# cpu.net
KiCad netlist of a schematic drawn in Altium Designer
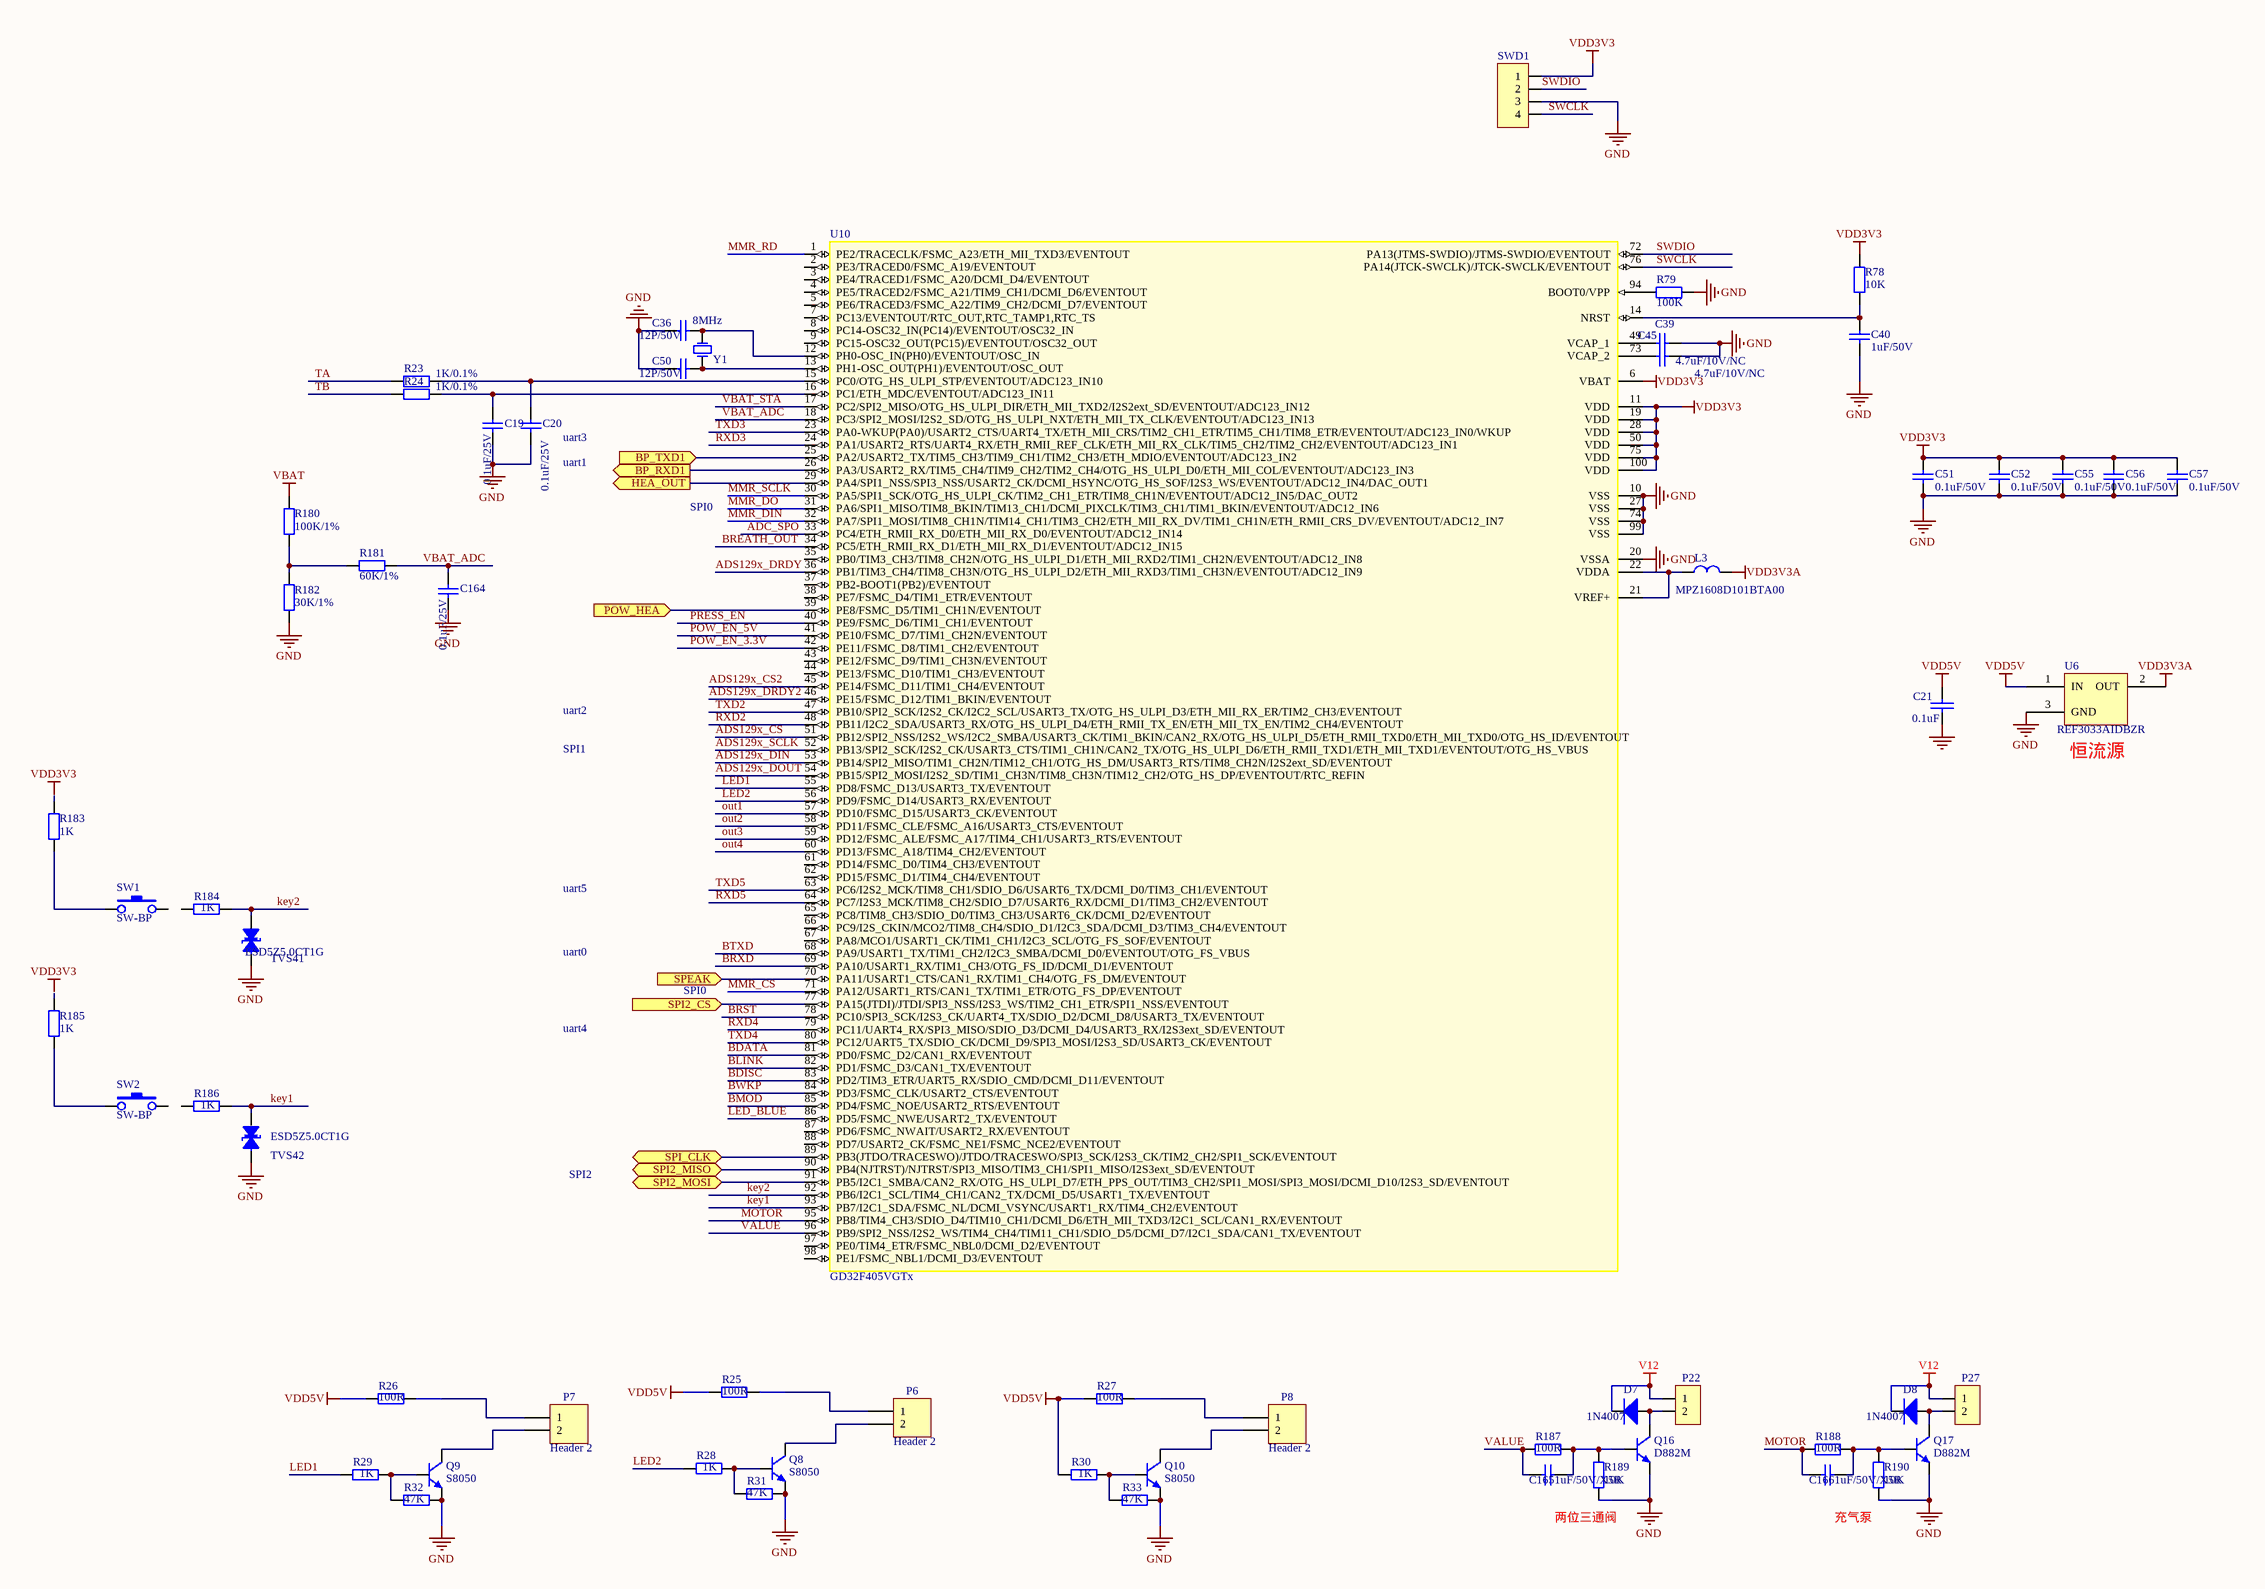
[diagram p0: cpu.SchDoc]

(export (version "E")
  (design (tool "Eeschema 10.0.6"))
  (components
    (comp (ref "C19")
      (value "0.1uF/25V")
      (footprint "SMD-0603C")
      (description "贴片电容 5%")
      (libsource (lib "XiaoyI") (part "CAP4"))
    )
    (comp (ref "C20")
      (value "0.1uF/25V")
      (footprint "SMD-0603C")
      (description "贴片电容 5%")
      (libsource (lib "XiaoyI") (part "CAP4"))
    )
    (comp (ref "C21")
      (value "0.1uF")
      (footprint "0603C")
      (description "Capacitor")
      (libsource (lib "*") (part "CAP"))
    )
    (comp (ref "C36")
      (value "12P/50V")
      (footprint "SMD-0603C")
      (description "贴片电容 5%")
      (libsource (lib "XiaoyI") (part "CAP4"))
    )
    (comp (ref "C39")
      (value "4.7uF/10V/NC")
      (footprint "SMD-0603C")
      (description "贴片电容 20%")
      (libsource (lib "XiaoyI") (part "CAP4"))
    )
    (comp (ref "C40")
      (value "1uF/50V")
      (footprint "SMD-0603C")
      (description "贴片电容 20%")
      (libsource (lib "XiaoyI") (part "CAP4"))
    )
    (comp (ref "C45")
      (value "4.7uF/10V/NC")
      (footprint "SMD-0603C")
      (description "贴片电容 20%")
      (libsource (lib "XiaoyI") (part "CAP4"))
    )
    (comp (ref "C50")
      (value "12P/50V")
      (footprint "SMD-0603C")
      (description "贴片电容 5%")
      (libsource (lib "XiaoyI") (part "CAP4"))
    )
    (comp (ref "C51")
      (value "0.1uF/50V")
      (footprint "SMD-0603C")
      (description "贴片电容 20%")
      (libsource (lib "XiaoyI") (part "CAP4"))
    )
    (comp (ref "C52")
      (value "0.1uF/50V")
      (footprint "SMD-0603C")
      (description "贴片电容 20%")
      (libsource (lib "XiaoyI") (part "CAP4"))
    )
    (comp (ref "C55")
      (value "0.1uF/50V")
      (footprint "SMD-0603C")
      (description "贴片电容 20%")
      (libsource (lib "XiaoyI") (part "CAP4"))
    )
    (comp (ref "C56")
      (value "0.1uF/50V")
      (footprint "SMD-0603C")
      (description "贴片电容 20%")
      (libsource (lib "XiaoyI") (part "CAP4"))
    )
    (comp (ref "C57")
      (value "0.1uF/50V")
      (footprint "SMD-0603C")
      (description "贴片电容 20%")
      (libsource (lib "XiaoyI") (part "CAP4"))
    )
    (comp (ref "C164")
      (value "0.1uF/25V")
      (footprint "SMD-0603C")
      (description "贴片电容 5%")
      (libsource (lib "XiaoyI") (part "CAP4"))
    )
    (comp (ref "C165")
      (value "1uF/50V/X5R")
      (footprint "SMD-0603C")
      (description "贴片电容 20%")
      (libsource (lib "XiaoyI") (part "CAP4"))
    )
    (comp (ref "C166")
      (value "1uF/50V/X5R")
      (footprint "SMD-0603C")
      (description "贴片电容 20%")
      (libsource (lib "XiaoyI") (part "CAP4"))
    )
    (comp (ref "D7")
      (value "1N4007")
      (footprint "DO-214-AC")
      (description "二极管 M7")
      (libsource (lib "XiaoyI") (part "DIODE2"))
    )
    (comp (ref "D8")
      (value "1N4007")
      (footprint "DO-214-AC")
      (description "二极管 M7")
      (libsource (lib "XiaoyI") (part "DIODE2"))
    )
    (comp (ref "L3")
      (value "MPZ1608D101BTA00")
      (footprint "SMD-0603")
      (description "磁珠电感 100R 100MHz")
      (libsource (lib "XiaoyI") (part "CIZHU1"))
    )
    (comp (ref "P6")
      (value "Header 2")
      (footprint "2X2.54MMZ")
      (description "Header, 2-Pin")
      (fields (field (name "PUBLISHER") "Altium Limited"))
      (libsource (lib "Miscellaneous Connectors") (part "Header 2"))
    )
    (comp (ref "P7")
      (value "Header 2")
      (footprint "2X2.54MMZ")
      (description "Header, 2-Pin")
      (fields (field (name "PUBLISHER") "Altium Limited"))
      (libsource (lib "Miscellaneous Connectors") (part "Header 2"))
    )
    (comp (ref "P8")
      (value "Header 2")
      (footprint "2X2.54MMZ")
      (description "Header, 2-Pin")
      (fields (field (name "PUBLISHER") "Altium Limited"))
      (libsource (lib "Miscellaneous Connectors") (part "Header 2"))
    )
    (comp (ref "P22")
      (value "VH2.54-2P")
      (footprint "2X2.54MMZ")
      (description "2.54mm- 2P立贴")
      (libsource (lib "XiaoyI") (part "SIP-2"))
    )
    (comp (ref "P27")
      (value "VH2.54-2P")
      (footprint "2X2.54MMZ")
      (description "2.54mm- 2P立贴")
      (libsource (lib "XiaoyI") (part "SIP-2"))
    )
    (comp (ref "Q8")
      (value "S8050")
      (footprint "SOT-23")
      (description "NPN")
      (libsource (lib "XiaoyI") (part "NPN-1"))
    )
    (comp (ref "Q9")
      (value "S8050")
      (footprint "SOT-23")
      (description "NPN")
      (libsource (lib "XiaoyI") (part "NPN-1"))
    )
    (comp (ref "Q10")
      (value "S8050")
      (footprint "SOT-23")
      (description "NPN")
      (libsource (lib "XiaoyI") (part "NPN-1"))
    )
    (comp (ref "Q16")
      (value "D882M")
      (footprint "SOT-89-3")
      (description "NPN TO252")
      (libsource (lib "XiaoyI") (part "NPN-TO252"))
    )
    (comp (ref "Q17")
      (value "D882M")
      (footprint "SOT-89-3")
      (description "NPN TO252")
      (libsource (lib "XiaoyI") (part "NPN-TO252"))
    )
    (comp (ref "R23")
      (value "1K/0.1%")
      (footprint "SMD-0603")
      (description "贴片电阻 1%")
      (libsource (lib "") (part "RES2_2"))
    )
    (comp (ref "R24")
      (value "1K/0.1%")
      (footprint "SMD-0603")
      (description "贴片电阻 1%")
      (libsource (lib "") (part "RES2_2"))
    )
    (comp (ref "R25")
      (value "100R")
      (footprint "SMD-0805")
      (description "贴片电阻 5%")
      (libsource (lib "") (part "RES0_1"))
    )
    (comp (ref "R26")
      (value "100R")
      (footprint "SMD-0805")
      (description "贴片电阻 5%")
      (libsource (lib "") (part "RES0_1"))
    )
    (comp (ref "R27")
      (value "100R")
      (footprint "SMD-0805")
      (description "贴片电阻 5%")
      (libsource (lib "") (part "RES0_1"))
    )
    (comp (ref "R28")
      (value "1K")
      (footprint "SMD-0603")
      (description "贴片电阻 5%")
      (libsource (lib "ABB") (part "RES0"))
    )
    (comp (ref "R29")
      (value "1K")
      (footprint "SMD-0603")
      (description "贴片电阻 5%")
      (libsource (lib "ABB") (part "RES0"))
    )
    (comp (ref "R30")
      (value "1K")
      (footprint "SMD-0603")
      (description "贴片电阻 5%")
      (libsource (lib "ABB") (part "RES0"))
    )
    (comp (ref "R31")
      (value "47K")
      (footprint "SMD-0603")
      (description "贴片电阻 5%")
      (libsource (lib "ABB") (part "RES0"))
    )
    (comp (ref "R32")
      (value "47K")
      (footprint "SMD-0603")
      (description "贴片电阻 5%")
      (libsource (lib "ABB") (part "RES0"))
    )
    (comp (ref "R33")
      (value "47K")
      (footprint "SMD-0603")
      (description "贴片电阻 5%")
      (libsource (lib "ABB") (part "RES0"))
    )
    (comp (ref "R78")
      (value "10K")
      (footprint "SMD-0603")
      (description "贴片电阻 5%")
      (libsource (lib "") (part "RES2_1"))
    )
    (comp (ref "R79")
      (value "100K")
      (footprint "SMD-0603")
      (description "贴片电阻 5%")
      (libsource (lib "") (part "RES2_2"))
    )
    (comp (ref "R180")
      (value "100K/1%")
      (footprint "SMD-0603")
      (description "贴片电阻 5%")
      (libsource (lib "XiaoyI") (part "RES2"))
    )
    (comp (ref "R181")
      (value "60K/1%")
      (footprint "SMD-0603")
      (description "贴片电阻 5%")
      (libsource (lib "") (part "RES2_3"))
    )
    (comp (ref "R182")
      (value "30K/1%")
      (footprint "SMD-0603")
      (description "贴片电阻 5%")
      (libsource (lib "XiaoyI") (part "RES2"))
    )
    (comp (ref "R183")
      (value "1K")
      (footprint "SMD-0603")
      (description "贴片电阻 5%")
      (libsource (lib "") (part "RES2_1"))
    )
    (comp (ref "R184")
      (value "1K")
      (footprint "SMD-0603")
      (description "贴片电阻 5%")
      (libsource (lib "") (part "RES2_3"))
    )
    (comp (ref "R185")
      (value "1K")
      (footprint "SMD-0603")
      (description "贴片电阻 5%")
      (libsource (lib "") (part "RES2_1"))
    )
    (comp (ref "R186")
      (value "1K")
      (footprint "SMD-0603")
      (description "贴片电阻 5%")
      (libsource (lib "") (part "RES2_3"))
    )
    (comp (ref "R187")
      (value "100R")
      (footprint "SMD-0603")
      (description "贴片电阻 5%")
      (libsource (lib "XiaoyI") (part "RES-SOP"))
    )
    (comp (ref "R188")
      (value "100R")
      (footprint "SMD-0603")
      (description "贴片电阻 5%")
      (libsource (lib "XiaoyI") (part "RES-SOP"))
    )
    (comp (ref "R189")
      (value "10K")
      (footprint "SMD-0603")
      (description "贴片电阻 5%")
      (libsource (lib "") (part "RES-SOP_1"))
    )
    (comp (ref "R190")
      (value "10K")
      (footprint "SMD-0603")
      (description "贴片电阻 5%")
      (libsource (lib "") (part "RES-SOP_1"))
    )
    (comp (ref "SW1")
      (value "SW-BP")
      (footprint "KEY_4X4")
      (description "3*6*3.5侧贴按键(编带)")
      (libsource (lib "XiaoyI") (part "SW-BP"))
    )
    (comp (ref "SW2")
      (value "SW-BP")
      (footprint "KEY_4X4")
      (description "3*6*3.5侧贴按键(编带)")
      (libsource (lib "XiaoyI") (part "SW-BP"))
    )
    (comp (ref "SWD1")
      (value "SIP-4 (NC)")
      (footprint "SIP-4")
      (description "ISP 下载")
      (libsource (lib "XiaoyI") (part "SIP-4"))
    )
    (comp (ref "TVS41")
      (value "ESD5Z5.0CT1G")
      (footprint "SOD-523")
      (description "ESD二极管")
      (libsource (lib "XiaoyI") (part "TVS-1"))
    )
    (comp (ref "TVS42")
      (value "ESD5Z5.0CT1G")
      (footprint "SOD-523")
      (description "ESD二极管")
      (libsource (lib "XiaoyI") (part "TVS-1"))
    )
    (comp (ref "U6")
      (value "REF3033AIDBZR")
      (footprint "SOT23-3")
      (libsource (lib "Schlib1") (part "REF3012"))
    )
    (comp (ref "U10")
      (value "GD32F405VGTx")
      (footprint "STM-LQFP100_N")
      (fields (field (name "MANUFACTURER") "STMicroelectronics") (field (name "PARTNUMBER") "STM32F405VGT6"))
      (libsource (lib "STM32F4") (part "STM32F405VGTx"))
    )
    (comp (ref "Y1")
      (value "8MHz")
      (footprint "XTAL-3225-2")
      (description "3225 贴片晶振")
      (libsource (lib "XiaoyI") (part "XTAL"))
    )
  )
  (nets
    (net (code "1") (name "/ADC_SPO") (class "Default")
      (node (ref "U10") (pin "33") (pinfunction "PC4/ETH_RMII_RX_D0/ETH_MII_RX_D0/EVENTOUT/ADC12_IN14_33") (pintype "bidirectional"))
    )
    (net (code "2") (name "/ADS129x_CS") (class "Default")
      (node (ref "U10") (pin "51") (pinfunction "PB12/SPI2_NSS/I2S2_WS/I2C2_SMBA/USART3_CK/TIM1_BKIN/CAN2_RX/OTG_HS_ULPI_D5/ETH_RMII_TXD0/ETH_MII_TXD0/OTG_HS_ID/EVENTOUT_51") (pintype "bidirectional"))
    )
    (net (code "3") (name "/ADS129x_CS2") (class "Default")
      (node (ref "U10") (pin "45") (pinfunction "PE14/FSMC_D11/TIM1_CH4/EVENTOUT_45") (pintype "bidirectional"))
    )
    (net (code "4") (name "/ADS129x_DIN") (class "Default")
      (node (ref "U10") (pin "53") (pinfunction "PB14/SPI2_MISO/TIM1_CH2N/TIM12_CH1/OTG_HS_DM/USART3_RTS/TIM8_CH2N/I2S2ext_SD/EVENTOUT_53") (pintype "bidirectional"))
    )
    (net (code "5") (name "/ADS129x_DOUT") (class "Default")
      (node (ref "U10") (pin "54") (pinfunction "PB15/SPI2_MOSI/I2S2_SD/TIM1_CH3N/TIM8_CH3N/TIM12_CH2/OTG_HS_DP/EVENTOUT/RTC_REFIN_54") (pintype "bidirectional"))
    )
    (net (code "6") (name "/ADS129x_DRDY") (class "Default")
      (node (ref "U10") (pin "36") (pinfunction "PB1/TIM3_CH4/TIM8_CH3N/OTG_HS_ULPI_D2/ETH_MII_RXD3/TIM1_CH3N/EVENTOUT/ADC12_IN9_36") (pintype "bidirectional"))
    )
    (net (code "7") (name "/ADS129x_DRDY2") (class "Default")
      (node (ref "U10") (pin "46") (pinfunction "PE15/FSMC_D12/TIM1_BKIN/EVENTOUT_46") (pintype "bidirectional"))
    )
    (net (code "8") (name "/ADS129x_SCLK") (class "Default")
      (node (ref "U10") (pin "52") (pinfunction "PB13/SPI2_SCK/I2S2_CK/USART3_CTS/TIM1_CH1N/CAN2_TX/OTG_HS_ULPI_D6/ETH_RMII_TXD1/ETH_MII_TXD1/EVENTOUT/OTG_HS_VBUS_52") (pintype "bidirectional"))
    )
    (net (code "9") (name "/BDATA") (class "Default")
      (node (ref "U10") (pin "81") (pinfunction "PD0/FSMC_D2/CAN1_RX/EVENTOUT_81") (pintype "bidirectional"))
    )
    (net (code "10") (name "/BDISC") (class "Default")
      (node (ref "U10") (pin "83") (pinfunction "PD2/TIM3_ETR/UART5_RX/SDIO_CMD/DCMI_D11/EVENTOUT_83") (pintype "bidirectional"))
    )
    (net (code "11") (name "/BLINK") (class "Default")
      (node (ref "U10") (pin "82") (pinfunction "PD1/FSMC_D3/CAN1_TX/EVENTOUT_82") (pintype "bidirectional"))
    )
    (net (code "12") (name "/BMOD") (class "Default")
      (node (ref "U10") (pin "85") (pinfunction "PD4/FSMC_NOE/USART2_RTS/EVENTOUT_85") (pintype "bidirectional"))
    )
    (net (code "13") (name "/BP_RXD1") (class "Default")
      (node (ref "U10") (pin "26") (pinfunction "PA3/USART2_RX/TIM5_CH4/TIM9_CH2/TIM2_CH4/OTG_HS_ULPI_D0/ETH_MII_COL/EVENTOUT/ADC123_IN3_26") (pintype "bidirectional"))
    )
    (net (code "14") (name "/BP_TXD1") (class "Default")
      (node (ref "U10") (pin "25") (pinfunction "PA2/USART2_TX/TIM5_CH3/TIM9_CH1/TIM2_CH3/ETH_MDIO/EVENTOUT/ADC123_IN2_25") (pintype "bidirectional"))
    )
    (net (code "15") (name "/BREATH_OUT") (class "Default")
      (node (ref "U10") (pin "34") (pinfunction "PC5/ETH_RMII_RX_D1/ETH_MII_RX_D1/EVENTOUT/ADC12_IN15_34") (pintype "bidirectional"))
    )
    (net (code "16") (name "/BRST") (class "Default")
      (node (ref "U10") (pin "78") (pinfunction "PC10/SPI3_SCK/I2S3_CK/UART4_TX/SDIO_D2/DCMI_D8/USART3_TX/EVENTOUT_78") (pintype "bidirectional"))
    )
    (net (code "17") (name "/BRXD") (class "Default")
      (node (ref "U10") (pin "69") (pinfunction "PA10/USART1_RX/TIM1_CH3/OTG_FS_ID/DCMI_D1/EVENTOUT_69") (pintype "bidirectional"))
    )
    (net (code "18") (name "/BTXD") (class "Default")
      (node (ref "U10") (pin "68") (pinfunction "PA9/USART1_TX/TIM1_CH2/I2C3_SMBA/DCMI_D0/EVENTOUT/OTG_FS_VBUS_68") (pintype "bidirectional"))
    )
    (net (code "19") (name "/BWKP") (class "Default")
      (node (ref "U10") (pin "84") (pinfunction "PD3/FSMC_CLK/USART2_CTS/EVENTOUT_84") (pintype "bidirectional"))
    )
    (net (code "20") (name "/HEA_OUT") (class "Default")
      (node (ref "U10") (pin "29") (pinfunction "PA4/SPI1_NSS/SPI3_NSS/USART2_CK/DCMI_HSYNC/OTG_HS_SOF/I2S3_WS/EVENTOUT/ADC12_IN4/DAC_OUT1_29") (pintype "bidirectional"))
    )
    (net (code "21") (name "/LED1") (class "Default")
      (node (ref "R29") (pin "1") (pinfunction "1_1") (pintype "passive"))
      (node (ref "U10") (pin "55") (pinfunction "PD8/FSMC_D13/USART3_TX/EVENTOUT_55") (pintype "bidirectional"))
    )
    (net (code "22") (name "/LED2") (class "Default")
      (node (ref "R28") (pin "1") (pinfunction "1_1") (pintype "passive"))
      (node (ref "U10") (pin "56") (pinfunction "PD9/FSMC_D14/USART3_RX/EVENTOUT_56") (pintype "bidirectional"))
    )
    (net (code "23") (name "/LED_BLUE") (class "Default")
      (node (ref "U10") (pin "86") (pinfunction "PD5/FSMC_NWE/USART2_TX/EVENTOUT_86") (pintype "bidirectional"))
    )
    (net (code "24") (name "/MMR_CS") (class "Default")
      (node (ref "U10") (pin "71") (pinfunction "PA12/USART1_RTS/CAN1_TX/TIM1_ETR/OTG_FS_DP/EVENTOUT_71") (pintype "bidirectional"))
    )
    (net (code "25") (name "/MMR_DIN") (class "Default")
      (node (ref "U10") (pin "32") (pinfunction "PA7/SPI1_MOSI/TIM8_CH1N/TIM14_CH1/TIM3_CH2/ETH_MII_RX_DV/TIM1_CH1N/ETH_RMII_CRS_DV/EVENTOUT/ADC12_IN7_32") (pintype "bidirectional"))
    )
    (net (code "26") (name "/MMR_DO") (class "Default")
      (node (ref "U10") (pin "31") (pinfunction "PA6/SPI1_MISO/TIM8_BKIN/TIM13_CH1/DCMI_PIXCLK/TIM3_CH1/TIM1_BKIN/EVENTOUT/ADC12_IN6_31") (pintype "bidirectional"))
    )
    (net (code "27") (name "/MMR_RD") (class "Default")
      (node (ref "U10") (pin "1") (pinfunction "PE2/TRACECLK/FSMC_A23/ETH_MII_TXD3/EVENTOUT_1") (pintype "bidirectional"))
    )
    (net (code "28") (name "/MMR_SCLK") (class "Default")
      (node (ref "U10") (pin "30") (pinfunction "PA5/SPI1_SCK/OTG_HS_ULPI_CK/TIM2_CH1_ETR/TIM8_CH1N/EVENTOUT/ADC12_IN5/DAC_OUT2_30") (pintype "bidirectional"))
    )
    (net (code "29") (name "/MOTOR") (class "Default")
      (node (ref "C166") (pin "2") (pinfunction "2_2") (pintype "passive"))
      (node (ref "R188") (pin "2") (pinfunction "2_2") (pintype "passive"))
      (node (ref "U10") (pin "95") (pinfunction "PB8/TIM4_CH3/SDIO_D4/TIM10_CH1/DCMI_D6/ETH_MII_TXD3/I2C1_SCL/CAN1_RX/EVENTOUT_95") (pintype "bidirectional"))
    )
    (net (code "30") (name "/POW_EN_3.3V") (class "Default")
      (node (ref "U10") (pin "42") (pinfunction "PE11/FSMC_D8/TIM1_CH2/EVENTOUT_42") (pintype "bidirectional"))
    )
    (net (code "31") (name "/POW_EN_5V") (class "Default")
      (node (ref "U10") (pin "41") (pinfunction "PE10/FSMC_D7/TIM1_CH2N/EVENTOUT_41") (pintype "bidirectional"))
    )
    (net (code "32") (name "/POW_HEA") (class "Default")
      (node (ref "U10") (pin "39") (pinfunction "PE8/FSMC_D5/TIM1_CH1N/EVENTOUT_39") (pintype "bidirectional"))
    )
    (net (code "33") (name "/PRESS_EN") (class "Default")
      (node (ref "U10") (pin "40") (pinfunction "PE9/FSMC_D6/TIM1_CH1/EVENTOUT_40") (pintype "bidirectional"))
    )
    (net (code "34") (name "/RXD2") (class "Default")
      (node (ref "U10") (pin "48") (pinfunction "PB11/I2C2_SDA/USART3_RX/OTG_HS_ULPI_D4/ETH_RMII_TX_EN/ETH_MII_TX_EN/TIM2_CH4/EVENTOUT_48") (pintype "bidirectional"))
    )
    (net (code "35") (name "/RXD3") (class "Default")
      (node (ref "U10") (pin "24") (pinfunction "PA1/USART2_RTS/UART4_RX/ETH_RMII_REF_CLK/ETH_MII_RX_CLK/TIM5_CH2/TIM2_CH2/EVENTOUT/ADC123_IN1_24") (pintype "bidirectional"))
    )
    (net (code "36") (name "/RXD4") (class "Default")
      (node (ref "U10") (pin "79") (pinfunction "PC11/UART4_RX/SPI3_MISO/SDIO_D3/DCMI_D4/USART3_RX/I2S3ext_SD/EVENTOUT_79") (pintype "bidirectional"))
    )
    (net (code "37") (name "/RXD5") (class "Default")
      (node (ref "U10") (pin "64") (pinfunction "PC7/I2S3_MCK/TIM8_CH2/SDIO_D7/USART6_RX/DCMI_D1/TIM3_CH2/EVENTOUT_64") (pintype "bidirectional"))
    )
    (net (code "38") (name "/SPEAK") (class "Default")
      (node (ref "U10") (pin "70") (pinfunction "PA11/USART1_CTS/CAN1_RX/TIM1_CH4/OTG_FS_DM/EVENTOUT_70") (pintype "bidirectional"))
    )
    (net (code "39") (name "/SPI2_CS") (class "Default")
      (node (ref "U10") (pin "77") (pinfunction "PA15(JTDI)/JTDI/SPI3_NSS/I2S3_WS/TIM2_CH1_ETR/SPI1_NSS/EVENTOUT_77") (pintype "bidirectional"))
    )
    (net (code "40") (name "/SPI2_MISO") (class "Default")
      (node (ref "U10") (pin "90") (pinfunction "PB4(NJTRST)/NJTRST/SPI3_MISO/TIM3_CH1/SPI1_MISO/I2S3ext_SD/EVENTOUT_90") (pintype "bidirectional"))
    )
    (net (code "41") (name "/SPI2_MOSI") (class "Default")
      (node (ref "U10") (pin "91") (pinfunction "PB5/I2C1_SMBA/CAN2_RX/OTG_HS_ULPI_D7/ETH_PPS_OUT/TIM3_CH2/SPI1_MOSI/SPI3_MOSI/DCMI_D10/I2S3_SD/EVENTOUT_91") (pintype "bidirectional"))
    )
    (net (code "42") (name "/SPI_CLK") (class "Default")
      (node (ref "U10") (pin "89") (pinfunction "PB3(JTDO/TRACESWO)/JTDO/TRACESWO/SPI3_SCK/I2S3_CK/TIM2_CH2/SPI1_SCK/EVENTOUT_89") (pintype "bidirectional"))
    )
    (net (code "43") (name "/SWCLK") (class "Default")
      (node (ref "SWD1") (pin "4") (pinfunction "4_4") (pintype "passive"))
      (node (ref "U10") (pin "76") (pinfunction "PA14(JTCK-SWCLK)/JTCK-SWCLK/EVENTOUT_76") (pintype "bidirectional"))
    )
    (net (code "44") (name "/SWDIO") (class "Default")
      (node (ref "SWD1") (pin "2") (pinfunction "2_2") (pintype "passive"))
      (node (ref "U10") (pin "72") (pinfunction "PA13(JTMS-SWDIO)/JTMS-SWDIO/EVENTOUT_72") (pintype "bidirectional"))
    )
    (net (code "45") (name "/TA") (class "Default")
      (node (ref "R23") (pin "2") (pinfunction "2_2") (pintype "passive"))
    )
    (net (code "46") (name "/TB") (class "Default")
      (node (ref "R24") (pin "2") (pinfunction "2_2") (pintype "passive"))
    )
    (net (code "47") (name "/TXD2") (class "Default")
      (node (ref "U10") (pin "47") (pinfunction "PB10/SPI2_SCK/I2S2_CK/I2C2_SCL/USART3_TX/OTG_HS_ULPI_D3/ETH_MII_RX_ER/TIM2_CH3/EVENTOUT_47") (pintype "bidirectional"))
    )
    (net (code "48") (name "/TXD3") (class "Default")
      (node (ref "U10") (pin "23") (pinfunction "PA0-WKUP(PA0)/USART2_CTS/UART4_TX/ETH_MII_CRS/TIM2_CH1_ETR/TIM5_CH1/TIM8_ETR/EVENTOUT/ADC123_IN0/WKUP_23") (pintype "bidirectional"))
    )
    (net (code "49") (name "/TXD4") (class "Default")
      (node (ref "U10") (pin "80") (pinfunction "PC12/UART5_TX/SDIO_CK/DCMI_D9/SPI3_MOSI/I2S3_SD/USART3_CK/EVENTOUT_80") (pintype "bidirectional"))
    )
    (net (code "50") (name "/TXD5") (class "Default")
      (node (ref "U10") (pin "63") (pinfunction "PC6/I2S2_MCK/TIM8_CH1/SDIO_D6/USART6_TX/DCMI_D0/TIM3_CH1/EVENTOUT_63") (pintype "bidirectional"))
    )
    (net (code "51") (name "/VALUE") (class "Default")
      (node (ref "C165") (pin "2") (pinfunction "2_2") (pintype "passive"))
      (node (ref "R187") (pin "2") (pinfunction "2_2") (pintype "passive"))
      (node (ref "U10") (pin "96") (pinfunction "PB9/SPI2_NSS/I2S2_WS/TIM4_CH4/TIM11_CH1/SDIO_D5/DCMI_D7/I2C1_SDA/CAN1_TX/EVENTOUT_96") (pintype "bidirectional"))
    )
    (net (code "52") (name "/VBAT_ADC") (class "Default")
      (node (ref "C164") (pin "1") (pinfunction "1_1") (pintype "passive"))
      (node (ref "R181") (pin "2") (pinfunction "2_2") (pintype "passive"))
      (node (ref "U10") (pin "18") (pinfunction "PC3/SPI2_MOSI/I2S2_SD/OTG_HS_ULPI_NXT/ETH_MII_TX_CLK/EVENTOUT/ADC123_IN13_18") (pintype "bidirectional"))
    )
    (net (code "53") (name "/VBAT_STA") (class "Default")
      (node (ref "U10") (pin "17") (pinfunction "PC2/SPI2_MISO/OTG_HS_ULPI_DIR/ETH_MII_TXD2/I2S2ext_SD/EVENTOUT/ADC123_IN12_17") (pintype "bidirectional"))
    )
    (net (code "54") (name "/key1") (class "Default")
      (node (ref "R186") (pin "2") (pinfunction "2_2") (pintype "passive"))
      (node (ref "TVS42") (pin "1") (pinfunction "A_1") (pintype "passive"))
      (node (ref "U10") (pin "93") (pinfunction "PB7/I2C1_SDA/FSMC_NL/DCMI_VSYNC/USART1_RX/TIM4_CH2/EVENTOUT_93") (pintype "bidirectional"))
    )
    (net (code "55") (name "/key2") (class "Default")
      (node (ref "R184") (pin "2") (pinfunction "2_2") (pintype "passive"))
      (node (ref "TVS41") (pin "1") (pinfunction "A_1") (pintype "passive"))
      (node (ref "U10") (pin "92") (pinfunction "PB6/I2C1_SCL/TIM4_CH1/CAN2_TX/DCMI_D5/USART1_TX/EVENTOUT_92") (pintype "bidirectional"))
    )
    (net (code "56") (name "/out1") (class "Default")
      (node (ref "U10") (pin "57") (pinfunction "PD10/FSMC_D15/USART3_CK/EVENTOUT_57") (pintype "bidirectional"))
    )
    (net (code "57") (name "/out2") (class "Default")
      (node (ref "U10") (pin "58") (pinfunction "PD11/FSMC_CLE/FSMC_A16/USART3_CTS/EVENTOUT_58") (pintype "bidirectional"))
    )
    (net (code "58") (name "/out3") (class "Default")
      (node (ref "U10") (pin "59") (pinfunction "PD12/FSMC_ALE/FSMC_A17/TIM4_CH1/USART3_RTS/EVENTOUT_59") (pintype "bidirectional"))
    )
    (net (code "59") (name "/out4") (class "Default")
      (node (ref "U10") (pin "60") (pinfunction "PD13/FSMC_A18/TIM4_CH2/EVENTOUT_60") (pintype "bidirectional"))
    )
    (net (code "60") (name "GND") (class "Default")
      (node (ref "C164") (pin "2") (pinfunction "2_2") (pintype "passive"))
      (node (ref "C19") (pin "2") (pinfunction "2_2") (pintype "passive"))
      (node (ref "C20") (pin "2") (pinfunction "2_2") (pintype "passive"))
      (node (ref "C21") (pin "2") (pinfunction "2_2") (pintype "passive"))
      (node (ref "C36") (pin "2") (pinfunction "2_2") (pintype "passive"))
      (node (ref "C39") (pin "1") (pinfunction "1_1") (pintype "passive"))
      (node (ref "C40") (pin "1") (pinfunction "1_1") (pintype "passive"))
      (node (ref "C45") (pin "1") (pinfunction "1_1") (pintype "passive"))
      (node (ref "C50") (pin "2") (pinfunction "2_2") (pintype "passive"))
      (node (ref "C51") (pin "1") (pinfunction "1_1") (pintype "passive"))
      (node (ref "C52") (pin "1") (pinfunction "1_1") (pintype "passive"))
      (node (ref "C55") (pin "1") (pinfunction "1_1") (pintype "passive"))
      (node (ref "C56") (pin "1") (pinfunction "1_1") (pintype "passive"))
      (node (ref "C57") (pin "1") (pinfunction "1_1") (pintype "passive"))
      (node (ref "Q10") (pin "2") (pinfunction "E_2") (pintype "passive"))
      (node (ref "Q16") (pin "3") (pinfunction "E_3") (pintype "passive"))
      (node (ref "Q17") (pin "3") (pinfunction "E_3") (pintype "passive"))
      (node (ref "Q8") (pin "2") (pinfunction "E_2") (pintype "passive"))
      (node (ref "Q9") (pin "2") (pinfunction "E_2") (pintype "passive"))
      (node (ref "R182") (pin "2") (pinfunction "2_2") (pintype "passive"))
      (node (ref "R189") (pin "2") (pinfunction "2_2") (pintype "passive"))
      (node (ref "R190") (pin "2") (pinfunction "2_2") (pintype "passive"))
      (node (ref "R31") (pin "2") (pinfunction "2_2") (pintype "passive"))
      (node (ref "R32") (pin "2") (pinfunction "2_2") (pintype "passive"))
      (node (ref "R33") (pin "2") (pinfunction "2_2") (pintype "passive"))
      (node (ref "R79") (pin "1") (pinfunction "1_1") (pintype "passive"))
      (node (ref "SWD1") (pin "3") (pinfunction "3_3") (pintype "passive"))
      (node (ref "TVS41") (pin "2") (pinfunction "B_2") (pintype "passive"))
      (node (ref "TVS42") (pin "2") (pinfunction "B_2") (pintype "passive"))
      (node (ref "U10") (pin "10") (pinfunction "VSS_10") (pintype "power_in"))
      (node (ref "U10") (pin "20") (pinfunction "VSSA_20") (pintype "power_in"))
      (node (ref "U10") (pin "27") (pinfunction "VSS_27") (pintype "power_in"))
      (node (ref "U10") (pin "74") (pinfunction "VSS_74") (pintype "power_in"))
      (node (ref "U10") (pin "99") (pinfunction "VSS_99") (pintype "power_in"))
      (node (ref "U6") (pin "3") (pinfunction "GND_3") (pintype "passive"))
    )
    (net (code "61") (name "Net-(D7-A)") (class "Default")
      (node (ref "D7") (pin "1") (pinfunction "A_1") (pintype "passive"))
      (node (ref "P22") (pin "2") (pinfunction "2_2") (pintype "passive"))
      (node (ref "Q16") (pin "2") (pinfunction "C_2") (pintype "passive"))
    )
    (net (code "62") (name "Net-(D8-A)") (class "Default")
      (node (ref "D8") (pin "1") (pinfunction "A_1") (pintype "passive"))
      (node (ref "P27") (pin "2") (pinfunction "2_2") (pintype "passive"))
      (node (ref "Q17") (pin "2") (pinfunction "C_2") (pintype "passive"))
    )
    (net (code "63") (name "Net-(P6-Pad1)") (class "Default")
      (node (ref "P6") (pin "1") (pinfunction "1_1") (pintype "passive"))
      (node (ref "R25") (pin "1") (pinfunction "1_1") (pintype "passive"))
    )
    (net (code "64") (name "Net-(P7-Pad1)") (class "Default")
      (node (ref "P7") (pin "1") (pinfunction "1_1") (pintype "passive"))
      (node (ref "R26") (pin "1") (pinfunction "1_1") (pintype "passive"))
    )
    (net (code "65") (name "Net-(P8-Pad1)") (class "Default")
      (node (ref "P8") (pin "1") (pinfunction "1_1") (pintype "passive"))
      (node (ref "R27") (pin "1") (pinfunction "1_1") (pintype "passive"))
    )
    (net (code "66") (name "Net-(Q8-B)") (class "Default")
      (node (ref "Q8") (pin "1") (pinfunction "B_1") (pintype "passive"))
      (node (ref "R28") (pin "2") (pinfunction "2_2") (pintype "passive"))
      (node (ref "R31") (pin "1") (pinfunction "1_1") (pintype "passive"))
    )
    (net (code "67") (name "Net-(Q8-C)") (class "Default")
      (node (ref "P6") (pin "2") (pinfunction "2_2") (pintype "passive"))
      (node (ref "Q8") (pin "3") (pinfunction "C_3") (pintype "passive"))
    )
    (net (code "68") (name "Net-(Q9-B)") (class "Default")
      (node (ref "Q9") (pin "1") (pinfunction "B_1") (pintype "passive"))
      (node (ref "R29") (pin "2") (pinfunction "2_2") (pintype "passive"))
      (node (ref "R32") (pin "1") (pinfunction "1_1") (pintype "passive"))
    )
    (net (code "69") (name "Net-(Q9-C)") (class "Default")
      (node (ref "P7") (pin "2") (pinfunction "2_2") (pintype "passive"))
      (node (ref "Q9") (pin "3") (pinfunction "C_3") (pintype "passive"))
    )
    (net (code "70") (name "Net-(Q10-B)") (class "Default")
      (node (ref "Q10") (pin "1") (pinfunction "B_1") (pintype "passive"))
      (node (ref "R30") (pin "2") (pinfunction "2_2") (pintype "passive"))
      (node (ref "R33") (pin "1") (pinfunction "1_1") (pintype "passive"))
    )
    (net (code "71") (name "Net-(Q10-C)") (class "Default")
      (node (ref "P8") (pin "2") (pinfunction "2_2") (pintype "passive"))
      (node (ref "Q10") (pin "3") (pinfunction "C_3") (pintype "passive"))
    )
    (net (code "72") (name "Net-(Q16-B)") (class "Default")
      (node (ref "C165") (pin "1") (pinfunction "1_1") (pintype "passive"))
      (node (ref "Q16") (pin "1") (pinfunction "B_1") (pintype "passive"))
      (node (ref "R187") (pin "1") (pinfunction "1_1") (pintype "passive"))
      (node (ref "R189") (pin "1") (pinfunction "1_1") (pintype "passive"))
    )
    (net (code "73") (name "Net-(Q17-B)") (class "Default")
      (node (ref "C166") (pin "1") (pinfunction "1_1") (pintype "passive"))
      (node (ref "Q17") (pin "1") (pinfunction "B_1") (pintype "passive"))
      (node (ref "R188") (pin "1") (pinfunction "1_1") (pintype "passive"))
      (node (ref "R190") (pin "1") (pinfunction "1_1") (pintype "passive"))
    )
    (net (code "74") (name "Net-(R180-Pad2)") (class "Default")
      (node (ref "R180") (pin "2") (pinfunction "2_2") (pintype "passive"))
      (node (ref "R181") (pin "1") (pinfunction "1_1") (pintype "passive"))
      (node (ref "R182") (pin "1") (pinfunction "1_1") (pintype "passive"))
    )
    (net (code "75") (name "Net-(R183-Pad1)") (class "Default")
      (node (ref "R183") (pin "1") (pinfunction "1_1") (pintype "passive"))
      (node (ref "SW1") (pin "1") (pinfunction "1_1") (pintype "passive"))
    )
    (net (code "76") (name "Net-(R185-Pad1)") (class "Default")
      (node (ref "R185") (pin "1") (pinfunction "1_1") (pintype "passive"))
      (node (ref "SW2") (pin "1") (pinfunction "1_1") (pintype "passive"))
    )
    (net (code "77") (name "Net-(U10-BOOT0{slash}VPP)") (class "Default")
      (node (ref "R79") (pin "2") (pinfunction "2_2") (pintype "passive"))
      (node (ref "U10") (pin "94") (pinfunction "BOOT0/VPP_94") (pintype "input"))
    )
    (net (code "78") (name "Net-(U10-NRST)") (class "Default")
      (node (ref "C40") (pin "2") (pinfunction "2_2") (pintype "passive"))
      (node (ref "R78") (pin "1") (pinfunction "1_1") (pintype "passive"))
      (node (ref "U10") (pin "14") (pinfunction "NRST_14") (pintype "bidirectional"))
    )
    (net (code "79") (name "Net-(U10-PC0{slash}OTG_HS_ULPI_STP{slash}EVENTOUT{slash}ADC123_IN10)") (class "Default")
      (node (ref "C20") (pin "1") (pinfunction "1_1") (pintype "passive"))
      (node (ref "R23") (pin "1") (pinfunction "1_1") (pintype "passive"))
      (node (ref "U10") (pin "15") (pinfunction "PC0/OTG_HS_ULPI_STP/EVENTOUT/ADC123_IN10_15") (pintype "bidirectional"))
    )
    (net (code "80") (name "Net-(U10-PC1{slash}ETH_MDC{slash}EVENTOUT{slash}ADC123_IN11)") (class "Default")
      (node (ref "C19") (pin "1") (pinfunction "1_1") (pintype "passive"))
      (node (ref "R24") (pin "1") (pinfunction "1_1") (pintype "passive"))
      (node (ref "U10") (pin "16") (pinfunction "PC1/ETH_MDC/EVENTOUT/ADC123_IN11_16") (pintype "bidirectional"))
    )
    (net (code "81") (name "Net-(U10-PH0-OSC_IN(PH0){slash}EVENTOUT{slash}OSC_IN)") (class "Default")
      (node (ref "C36") (pin "1") (pinfunction "1_1") (pintype "passive"))
      (node (ref "U10") (pin "12") (pinfunction "PH0-OSC_IN(PH0)/EVENTOUT/OSC_IN_12") (pintype "bidirectional"))
      (node (ref "Y1") (pin "2") (pinfunction "OSC2_2") (pintype "passive"))
    )
    (net (code "82") (name "Net-(U10-PH1-OSC_OUT(PH1){slash}EVENTOUT{slash}OSC_OUT)") (class "Default")
      (node (ref "C50") (pin "1") (pinfunction "1_1") (pintype "passive"))
      (node (ref "U10") (pin "13") (pinfunction "PH1-OSC_OUT(PH1)/EVENTOUT/OSC_OUT_13") (pintype "bidirectional"))
      (node (ref "Y1") (pin "1") (pinfunction "OSC1_1") (pintype "passive"))
    )
    (net (code "83") (name "Net-(U10-VCAP_1)") (class "Default")
      (node (ref "C39") (pin "2") (pinfunction "2_2") (pintype "passive"))
      (node (ref "U10") (pin "49") (pinfunction "VCAP_1_49") (pintype "power_in"))
    )
    (net (code "84") (name "Net-(U10-VCAP_2)") (class "Default")
      (node (ref "C45") (pin "2") (pinfunction "2_2") (pintype "passive"))
      (node (ref "U10") (pin "73") (pinfunction "VCAP_2_73") (pintype "power_in"))
    )
    (net (code "85") (name "Net-(U10-VDDA)") (class "Default")
      (node (ref "L3") (pin "2") (pinfunction "2_2") (pintype "passive"))
      (node (ref "U10") (pin "21") (pinfunction "VREF+_21") (pintype "power_in"))
      (node (ref "U10") (pin "22") (pinfunction "VDDA_22") (pintype "power_in"))
    )
    (net (code "86") (name "V12") (class "Default")
      (node (ref "D7") (pin "2") (pinfunction "K_2") (pintype "passive"))
      (node (ref "D8") (pin "2") (pinfunction "K_2") (pintype "passive"))
      (node (ref "P22") (pin "1") (pinfunction "1_1") (pintype "passive"))
      (node (ref "P27") (pin "1") (pinfunction "1_1") (pintype "passive"))
    )
    (net (code "87") (name "VBAT") (class "Default")
      (node (ref "R180") (pin "1") (pinfunction "1_1") (pintype "passive"))
    )
    (net (code "88") (name "VDD3V3") (class "Default")
      (node (ref "C51") (pin "2") (pinfunction "2_2") (pintype "passive"))
      (node (ref "C52") (pin "2") (pinfunction "2_2") (pintype "passive"))
      (node (ref "C55") (pin "2") (pinfunction "2_2") (pintype "passive"))
      (node (ref "C56") (pin "2") (pinfunction "2_2") (pintype "passive"))
      (node (ref "C57") (pin "2") (pinfunction "2_2") (pintype "passive"))
      (node (ref "R78") (pin "2") (pinfunction "2_2") (pintype "passive"))
      (node (ref "SWD1") (pin "1") (pinfunction "1_1") (pintype "passive"))
      (node (ref "U10") (pin "100") (pinfunction "VDD_100") (pintype "power_in"))
      (node (ref "U10") (pin "11") (pinfunction "VDD_11") (pintype "power_in"))
      (node (ref "U10") (pin "19") (pinfunction "VDD_19") (pintype "power_in"))
      (node (ref "U10") (pin "28") (pinfunction "VDD_28") (pintype "power_in"))
      (node (ref "U10") (pin "50") (pinfunction "VDD_50") (pintype "power_in"))
      (node (ref "U10") (pin "6") (pinfunction "VBAT_6") (pintype "power_in"))
      (node (ref "U10") (pin "75") (pinfunction "VDD_75") (pintype "power_in"))
    )
    (net (code "89") (name "VDD3V3A") (class "Default")
      (node (ref "L3") (pin "1") (pinfunction "1_1") (pintype "passive"))
      (node (ref "U6") (pin "2") (pinfunction "OUT_2") (pintype "passive"))
    )
    (net (code "90") (name "VDD5V") (class "Default")
      (node (ref "C21") (pin "1") (pinfunction "1_1") (pintype "passive"))
      (node (ref "R25") (pin "2") (pinfunction "2_2") (pintype "passive"))
      (node (ref "R26") (pin "2") (pinfunction "2_2") (pintype "passive"))
      (node (ref "R27") (pin "2") (pinfunction "2_2") (pintype "passive"))
      (node (ref "R30") (pin "1") (pinfunction "1_1") (pintype "passive"))
      (node (ref "U6") (pin "1") (pinfunction "IN_1") (pintype "passive"))
    )
    (net (code "91") (name "unconnected-(R183-Pad2)") (class "Default")
      (node (ref "R183") (pin "2") (pinfunction "2_2") (pintype "passive"))
    )
    (net (code "92") (name "unconnected-(R184-Pad1)") (class "Default")
      (node (ref "R184") (pin "1") (pinfunction "1_1") (pintype "passive"))
    )
    (net (code "93") (name "unconnected-(R185-Pad2)") (class "Default")
      (node (ref "R185") (pin "2") (pinfunction "2_2") (pintype "passive"))
    )
    (net (code "94") (name "unconnected-(R186-Pad1)") (class "Default")
      (node (ref "R186") (pin "1") (pinfunction "1_1") (pintype "passive"))
    )
    (net (code "95") (name "unconnected-(SW1-Pad2)") (class "Default")
      (node (ref "SW1") (pin "2") (pinfunction "2_2") (pintype "passive"))
    )
    (net (code "96") (name "unconnected-(SW2-Pad2)") (class "Default")
      (node (ref "SW2") (pin "2") (pinfunction "2_2") (pintype "passive"))
    )
    (net (code "97") (name "unconnected-(U10-PA8{slash}MCO1{slash}USART1_CK{slash}TIM1_CH1{slash}I2C3_SCL{slash}OTG_FS_SOF{slash}EVENTOUT-Pad67)") (class "Default")
      (node (ref "U10") (pin "67") (pinfunction "PA8/MCO1/USART1_CK/TIM1_CH1/I2C3_SCL/OTG_FS_SOF/EVENTOUT_67") (pintype "bidirectional"))
    )
    (net (code "98") (name "unconnected-(U10-PB0{slash}TIM3_CH3{slash}TIM8_CH2N{slash}OTG_HS_ULPI_D1{slash}ETH_MII_RXD2{slash}TIM1_CH2N{slash}EVENTOUT{slash}ADC12_IN8-Pad35)") (class "Default")
      (node (ref "U10") (pin "35") (pinfunction "PB0/TIM3_CH3/TIM8_CH2N/OTG_HS_ULPI_D1/ETH_MII_RXD2/TIM1_CH2N/EVENTOUT/ADC12_IN8_35") (pintype "bidirectional"))
    )
    (net (code "99") (name "unconnected-(U10-PB2-BOOT1(PB2){slash}EVENTOUT-Pad37)") (class "Default")
      (node (ref "U10") (pin "37") (pinfunction "PB2-BOOT1(PB2)/EVENTOUT_37") (pintype "bidirectional"))
    )
    (net (code "100") (name "unconnected-(U10-PC8{slash}TIM8_CH3{slash}SDIO_D0{slash}TIM3_CH3{slash}USART6_CK{slash}DCMI_D2{slash}EVENTOUT-Pad65)") (class "Default")
      (node (ref "U10") (pin "65") (pinfunction "PC8/TIM8_CH3/SDIO_D0/TIM3_CH3/USART6_CK/DCMI_D2/EVENTOUT_65") (pintype "bidirectional"))
    )
    (net (code "101") (name "unconnected-(U10-PC9{slash}I2S_CKIN{slash}MCO2{slash}TIM8_CH4{slash}SDIO_D1{slash}I2C3_SDA{slash}DCMI_D3{slash}TIM3_CH4{slash}EVENTOUT-Pad66)") (class "Default")
      (node (ref "U10") (pin "66") (pinfunction "PC9/I2S_CKIN/MCO2/TIM8_CH4/SDIO_D1/I2C3_SDA/DCMI_D3/TIM3_CH4/EVENTOUT_66") (pintype "bidirectional"))
    )
    (net (code "102") (name "unconnected-(U10-PC13{slash}EVENTOUT{slash}RTC_OUT,RTC_TAMP1,RTC_TS-Pad7)") (class "Default")
      (node (ref "U10") (pin "7") (pinfunction "PC13/EVENTOUT/RTC_OUT,RTC_TAMP1,RTC_TS_7") (pintype "bidirectional"))
    )
    (net (code "103") (name "unconnected-(U10-PC14-OSC32_IN(PC14){slash}EVENTOUT{slash}OSC32_IN-Pad8)") (class "Default")
      (node (ref "U10") (pin "8") (pinfunction "PC14-OSC32_IN(PC14)/EVENTOUT/OSC32_IN_8") (pintype "bidirectional"))
    )
    (net (code "104") (name "unconnected-(U10-PC15-OSC32_OUT(PC15){slash}EVENTOUT{slash}OSC32_OUT-Pad9)") (class "Default")
      (node (ref "U10") (pin "9") (pinfunction "PC15-OSC32_OUT(PC15)/EVENTOUT/OSC32_OUT_9") (pintype "bidirectional"))
    )
    (net (code "105") (name "unconnected-(U10-PD6{slash}FSMC_NWAIT{slash}USART2_RX{slash}EVENTOUT-Pad87)") (class "Default")
      (node (ref "U10") (pin "87") (pinfunction "PD6/FSMC_NWAIT/USART2_RX/EVENTOUT_87") (pintype "bidirectional"))
    )
    (net (code "106") (name "unconnected-(U10-PD7{slash}USART2_CK{slash}FSMC_NE1{slash}FSMC_NCE2{slash}EVENTOUT-Pad88)") (class "Default")
      (node (ref "U10") (pin "88") (pinfunction "PD7/USART2_CK/FSMC_NE1/FSMC_NCE2/EVENTOUT_88") (pintype "bidirectional"))
    )
    (net (code "107") (name "unconnected-(U10-PD14{slash}FSMC_D0{slash}TIM4_CH3{slash}EVENTOUT-Pad61)") (class "Default")
      (node (ref "U10") (pin "61") (pinfunction "PD14/FSMC_D0/TIM4_CH3/EVENTOUT_61") (pintype "bidirectional"))
    )
    (net (code "108") (name "unconnected-(U10-PD15{slash}FSMC_D1{slash}TIM4_CH4{slash}EVENTOUT-Pad62)") (class "Default")
      (node (ref "U10") (pin "62") (pinfunction "PD15/FSMC_D1/TIM4_CH4/EVENTOUT_62") (pintype "bidirectional"))
    )
    (net (code "109") (name "unconnected-(U10-PE0{slash}TIM4_ETR{slash}FSMC_NBL0{slash}DCMI_D2{slash}EVENTOUT-Pad97)") (class "Default")
      (node (ref "U10") (pin "97") (pinfunction "PE0/TIM4_ETR/FSMC_NBL0/DCMI_D2/EVENTOUT_97") (pintype "bidirectional"))
    )
    (net (code "110") (name "unconnected-(U10-PE1{slash}FSMC_NBL1{slash}DCMI_D3{slash}EVENTOUT-Pad98)") (class "Default")
      (node (ref "U10") (pin "98") (pinfunction "PE1/FSMC_NBL1/DCMI_D3/EVENTOUT_98") (pintype "bidirectional"))
    )
    (net (code "111") (name "unconnected-(U10-PE3{slash}TRACED0{slash}FSMC_A19{slash}EVENTOUT-Pad2)") (class "Default")
      (node (ref "U10") (pin "2") (pinfunction "PE3/TRACED0/FSMC_A19/EVENTOUT_2") (pintype "bidirectional"))
    )
    (net (code "112") (name "unconnected-(U10-PE4{slash}TRACED1{slash}FSMC_A20{slash}DCMI_D4{slash}EVENTOUT-Pad3)") (class "Default")
      (node (ref "U10") (pin "3") (pinfunction "PE4/TRACED1/FSMC_A20/DCMI_D4/EVENTOUT_3") (pintype "bidirectional"))
    )
    (net (code "113") (name "unconnected-(U10-PE5{slash}TRACED2{slash}FSMC_A21{slash}TIM9_CH1{slash}DCMI_D6{slash}EVENTOUT-Pad4)") (class "Default")
      (node (ref "U10") (pin "4") (pinfunction "PE5/TRACED2/FSMC_A21/TIM9_CH1/DCMI_D6/EVENTOUT_4") (pintype "bidirectional"))
    )
    (net (code "114") (name "unconnected-(U10-PE6{slash}TRACED3{slash}FSMC_A22{slash}TIM9_CH2{slash}DCMI_D7{slash}EVENTOUT-Pad5)") (class "Default")
      (node (ref "U10") (pin "5") (pinfunction "PE6/TRACED3/FSMC_A22/TIM9_CH2/DCMI_D7/EVENTOUT_5") (pintype "bidirectional"))
    )
    (net (code "115") (name "unconnected-(U10-PE7{slash}FSMC_D4{slash}TIM1_ETR{slash}EVENTOUT-Pad38)") (class "Default")
      (node (ref "U10") (pin "38") (pinfunction "PE7/FSMC_D4/TIM1_ETR/EVENTOUT_38") (pintype "bidirectional"))
    )
    (net (code "116") (name "unconnected-(U10-PE12{slash}FSMC_D9{slash}TIM1_CH3N{slash}EVENTOUT-Pad43)") (class "Default")
      (node (ref "U10") (pin "43") (pinfunction "PE12/FSMC_D9/TIM1_CH3N/EVENTOUT_43") (pintype "bidirectional"))
    )
    (net (code "117") (name "unconnected-(U10-PE13{slash}FSMC_D10{slash}TIM1_CH3{slash}EVENTOUT-Pad44)") (class "Default")
      (node (ref "U10") (pin "44") (pinfunction "PE13/FSMC_D10/TIM1_CH3/EVENTOUT_44") (pintype "bidirectional"))
    )
  )
)
